# microSDport.net
KiCad netlist of a schematic drawn in EAGLE
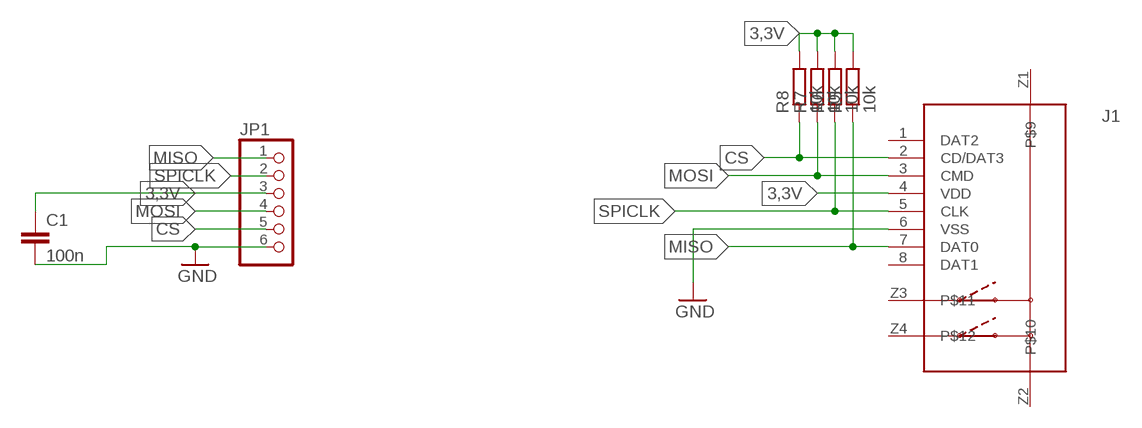
[diagram p0: schematic, sheet 1]

(export (version "E")
  (design (tool "Eeschema 10.0.6"))
  (components
    (comp (ref "C1")
      (value "100n")
      (footprint "eagle-import:C0805K")
      (libsource (lib "eagle-import") (part "C-EUC0805K"))
    )
    (comp (ref "J1")
      (value "693072010801")
      (footprint "eagle-import:693072010801")
      (libsource (lib "eagle-import") (part "693072010801"))
    )
    (comp (ref "JP1")
      (value "PINHD-1X6")
      (footprint "eagle-import:1X06")
      (libsource (lib "eagle-import") (part "PINHD-1X6"))
    )
    (comp (ref "R5")
      (value "10k")
      (footprint "eagle-import:R0805")
      (libsource (lib "eagle-import") (part "R-EU_R0805"))
    )
    (comp (ref "R6")
      (value "10k")
      (footprint "eagle-import:R0805")
      (libsource (lib "eagle-import") (part "R-EU_R0805"))
    )
    (comp (ref "R7")
      (value "10k")
      (footprint "eagle-import:R0805")
      (libsource (lib "eagle-import") (part "R-EU_R0805"))
    )
    (comp (ref "R8")
      (value "10k")
      (footprint "eagle-import:R0805")
      (libsource (lib "eagle-import") (part "R-EU_R0805"))
    )
  )
  (nets
    (net (code "1") (name "3,3V") (class "Default")
      (node (ref "C1") (pin "1") (pinfunction "1_1") (pintype "passive"))
      (node (ref "J1") (pin "4") (pinfunction "VDD_4") (pintype "bidirectional"))
      (node (ref "JP1") (pin "3") (pinfunction "3_3") (pintype "passive"))
      (node (ref "R5") (pin "2") (pinfunction "2_2") (pintype "passive"))
      (node (ref "R6") (pin "2") (pinfunction "2_2") (pintype "passive"))
      (node (ref "R7") (pin "2") (pinfunction "2_2") (pintype "passive"))
      (node (ref "R8") (pin "2") (pinfunction "2_2") (pintype "passive"))
    )
    (net (code "2") (name "CS") (class "Default")
      (node (ref "J1") (pin "2") (pinfunction "CD/DAT3_2") (pintype "bidirectional"))
      (node (ref "JP1") (pin "5") (pinfunction "5_5") (pintype "passive"))
      (node (ref "R8") (pin "1") (pinfunction "1_1") (pintype "passive"))
    )
    (net (code "3") (name "GND") (class "Default")
      (node (ref "C1") (pin "2") (pinfunction "2_2") (pintype "passive"))
      (node (ref "J1") (pin "6") (pinfunction "VSS_6") (pintype "bidirectional"))
      (node (ref "JP1") (pin "6") (pinfunction "6_6") (pintype "passive"))
    )
    (net (code "4") (name "MISO") (class "Default")
      (node (ref "J1") (pin "7") (pinfunction "DAT0_7") (pintype "bidirectional"))
      (node (ref "JP1") (pin "1") (pinfunction "1_1") (pintype "passive"))
      (node (ref "R5") (pin "1") (pinfunction "1_1") (pintype "passive"))
    )
    (net (code "5") (name "MOSI") (class "Default")
      (node (ref "J1") (pin "3") (pinfunction "CMD_3") (pintype "bidirectional"))
      (node (ref "JP1") (pin "4") (pinfunction "4_4") (pintype "passive"))
      (node (ref "R7") (pin "1") (pinfunction "1_1") (pintype "passive"))
    )
    (net (code "6") (name "SPICLK") (class "Default")
      (node (ref "J1") (pin "5") (pinfunction "CLK_5") (pintype "bidirectional"))
      (node (ref "JP1") (pin "2") (pinfunction "2_2") (pintype "passive"))
      (node (ref "R6") (pin "1") (pinfunction "1_1") (pintype "passive"))
    )
    (net (code "7") (name "unconnected-(J1-DAT1-Pad8)") (class "Default")
      (node (ref "J1") (pin "8") (pinfunction "DAT1_8") (pintype "bidirectional"))
    )
    (net (code "8") (name "unconnected-(J1-DAT2-Pad1)") (class "Default")
      (node (ref "J1") (pin "1") (pinfunction "DAT2_1") (pintype "bidirectional"))
    )
    (net (code "9") (name "unconnected-(J1-P$9-PadZ1)") (class "Default")
      (node (ref "J1") (pin "Z1") (pinfunction "P$9_Z1") (pintype "bidirectional"))
    )
    (net (code "10") (name "unconnected-(J1-P$10-PadZ2)") (class "Default")
      (node (ref "J1") (pin "Z2") (pinfunction "P$10_Z2") (pintype "bidirectional"))
    )
    (net (code "11") (name "unconnected-(J1-P$11-PadZ3)") (class "Default")
      (node (ref "J1") (pin "Z3") (pinfunction "P$11_Z3") (pintype "bidirectional"))
    )
    (net (code "12") (name "unconnected-(J1-P$12-PadZ4)") (class "Default")
      (node (ref "J1") (pin "Z4") (pinfunction "P$12_Z4") (pintype "bidirectional"))
    )
  )
)
